# Power.net
KiCad netlist of a schematic drawn in Altium Designer
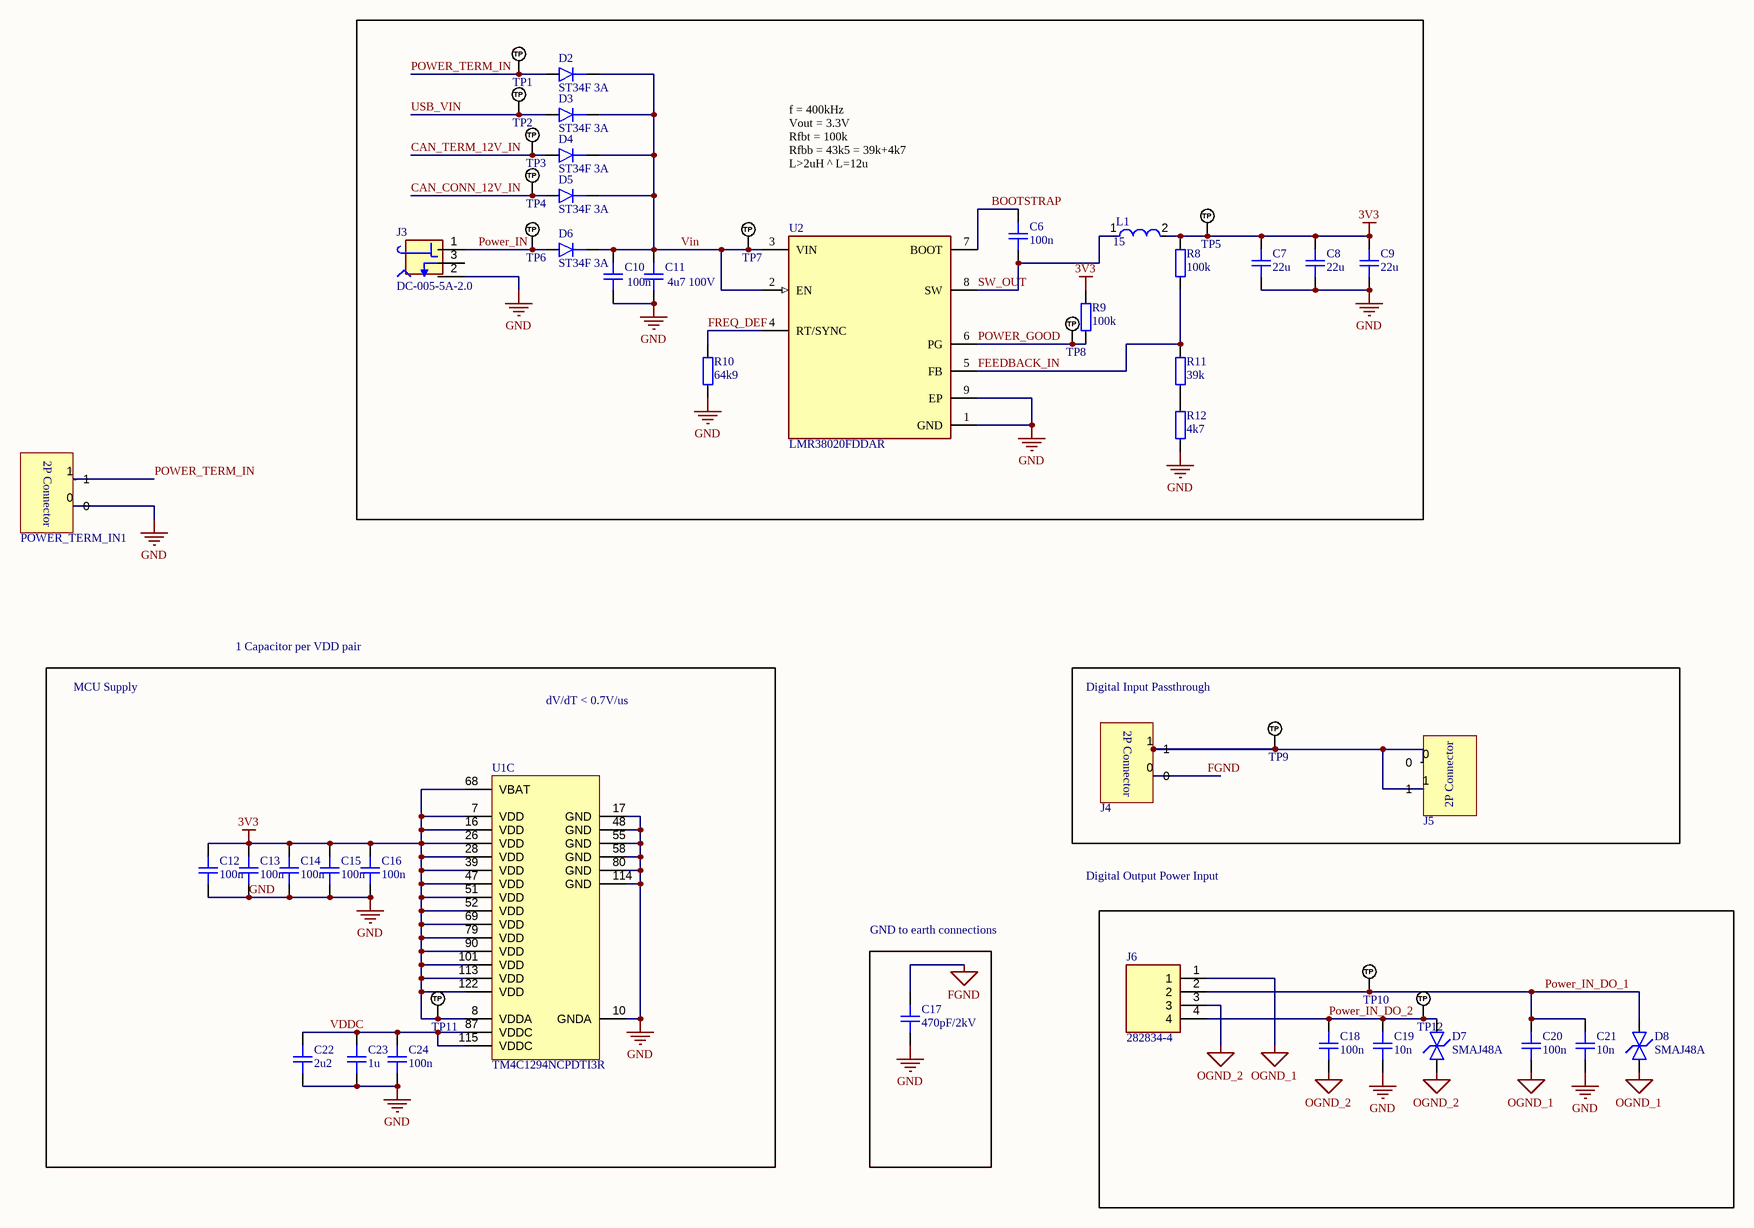
[diagram p0: Power.SchDoc]

(export (version "E")
  (design (tool "Eeschema 10.0.6"))
  (components
    (comp (ref "C6")
      (value "100n")
      (footprint "CAP_0402")
      (description "Capacitor SMD 0402")
      (libsource (lib "Schematic-Lib-PhilsLab") (part "CAP_0402"))
    )
    (comp (ref "C7")
      (value "22u")
      (footprint "CAP_1206")
      (description "Capacitor SMD 1206")
      (libsource (lib "Schematic-Lib-PhilsLab") (part "CAP_1206"))
    )
    (comp (ref "C8")
      (value "22u")
      (footprint "CAP_1206")
      (description "Capacitor SMD 1206")
      (libsource (lib "Schematic-Lib-PhilsLab") (part "CAP_1206"))
    )
    (comp (ref "C9")
      (value "22u")
      (footprint "CAP_1206")
      (description "Capacitor SMD 1206")
      (libsource (lib "Schematic-Lib-PhilsLab") (part "CAP_1206"))
    )
    (comp (ref "C10")
      (value "100n")
      (footprint "CAP_1206")
      (description "Capacitor SMD 1206")
      (libsource (lib "Schematic-Lib-PhilsLab") (part "CAP_1206"))
    )
    (comp (ref "C11")
      (value "4u7 100V")
      (footprint "CAP_1206")
      (description "Capacitor SMD 1206")
      (libsource (lib "Schematic-Lib-PhilsLab") (part "CAP_1206"))
    )
    (comp (ref "C12")
      (value "100n")
      (footprint "CAP_0402")
      (description "Capacitor SMD 0402")
      (libsource (lib "Schematic-Lib-PhilsLab") (part "CAP_0402"))
    )
    (comp (ref "C13")
      (value "100n")
      (footprint "CAP_0402")
      (description "Capacitor SMD 0402")
      (libsource (lib "Schematic-Lib-PhilsLab") (part "CAP_0402"))
    )
    (comp (ref "C14")
      (value "100n")
      (footprint "CAP_0402")
      (description "Capacitor SMD 0402")
      (libsource (lib "Schematic-Lib-PhilsLab") (part "CAP_0402"))
    )
    (comp (ref "C15")
      (value "100n")
      (footprint "CAP_0402")
      (description "Capacitor SMD 0402")
      (libsource (lib "Schematic-Lib-PhilsLab") (part "CAP_0402"))
    )
    (comp (ref "C16")
      (value "100n")
      (footprint "CAP_0402")
      (description "Capacitor SMD 0402")
      (libsource (lib "Schematic-Lib-PhilsLab") (part "CAP_0402"))
    )
    (comp (ref "C17")
      (value "470pF/2kV")
      (footprint "CAP_1206")
      (description "Capacitor SMD 1206")
      (libsource (lib "Schematic-Lib-PhilsLab") (part "CAP_1206"))
    )
    (comp (ref "C18")
      (value "100n")
      (footprint "CAP_0603")
      (description "Capacitor SMD 0603")
      (libsource (lib "Schematic-Lib-PhilsLab") (part "CAP_0603"))
    )
    (comp (ref "C19")
      (value "10n")
      (footprint "CAP_0603")
      (description "Capacitor SMD 0603")
      (libsource (lib "Schematic-Lib-PhilsLab") (part "CAP_0603"))
    )
    (comp (ref "C20")
      (value "100n")
      (footprint "CAP_0603")
      (description "Capacitor SMD 0603")
      (libsource (lib "Schematic-Lib-PhilsLab") (part "CAP_0603"))
    )
    (comp (ref "C21")
      (value "10n")
      (footprint "CAP_0603")
      (description "Capacitor SMD 0603")
      (libsource (lib "Schematic-Lib-PhilsLab") (part "CAP_0603"))
    )
    (comp (ref "C22")
      (value "2u2")
      (footprint "CAP_0402")
      (description "Capacitor SMD 0402")
      (libsource (lib "Schematic-Lib-PhilsLab") (part "CAP_0402"))
    )
    (comp (ref "C23")
      (value "1u")
      (footprint "CAP_0402")
      (description "Capacitor SMD 0402")
      (libsource (lib "Schematic-Lib-PhilsLab") (part "CAP_0402"))
    )
    (comp (ref "C24")
      (value "100n")
      (footprint "CAP_0402")
      (description "Capacitor SMD 0402")
      (libsource (lib "Schematic-Lib-PhilsLab") (part "CAP_0402"))
    )
    (comp (ref "D2")
      (value "ST34F 3A")
      (footprint "DO-214AC-2 (SMA)")
      (description "Diode SMD SMA (DO-214AA)")
      (libsource (lib "Schematic-Lib-PhilsLab") (part "D_SMA"))
    )
    (comp (ref "D3")
      (value "ST34F 3A")
      (footprint "DO-214AC-2 (SMA)")
      (description "Diode SMD SMA (DO-214AA)")
      (libsource (lib "Schematic-Lib-PhilsLab") (part "D_SMA"))
    )
    (comp (ref "D4")
      (value "ST34F 3A")
      (footprint "DO-214AC-2 (SMA)")
      (description "Diode SMD SMA (DO-214AA)")
      (libsource (lib "Schematic-Lib-PhilsLab") (part "D_SMA"))
    )
    (comp (ref "D5")
      (value "ST34F 3A")
      (footprint "DO-214AC-2 (SMA)")
      (description "Diode SMD SMA (DO-214AA)")
      (libsource (lib "Schematic-Lib-PhilsLab") (part "D_SMA"))
    )
    (comp (ref "D6")
      (value "ST34F 3A")
      (footprint "DO-214AC-2 (SMA)")
      (description "Diode SMD SMA (DO-214AA)")
      (libsource (lib "Schematic-Lib-PhilsLab") (part "D_SMA"))
    )
    (comp (ref "D7")
      (value "SMAJ48A")
      (footprint "DO-214AC-2 (SMA)")
      (description "Diode TVS / ESD Bidirectional SMC (DO-214AB)")
      (libsource (lib "Schematic-Lib-PhilsLab") (part "D_TVS_BI_SMC"))
    )
    (comp (ref "D8")
      (value "SMAJ48A")
      (footprint "DO-214AC-2 (SMA)")
      (description "Diode TVS / ESD Bidirectional SMC (DO-214AB)")
      (libsource (lib "Schematic-Lib-PhilsLab") (part "D_TVS_BI_SMC"))
    )
    (comp (ref "J3")
      (value "DC-005-5A-2.0")
      (footprint "XKB_DC-005-5A-2.0")
      (description "DC Power Receptacle Jack, Through Holeï¼ŒRight Angle")
      (fields (field (name "MF") "XKB Industrial Precision"))
      (libsource (lib "DIGI2") (part "DC-005-5A-2.0"))
    )
    (comp (ref "J4")
      (value "DG308-2.54-02P-12-00AH")
      (footprint "DG308-2.54-02P-12-00AH-Footprint-1")
      (description "1x2P -40℃~+105℃ 8A 130V Green 18~26 Straight 2.54mm 0.5~1 1 2 Plugin,P=2.54mm Screw terminal ROHS")
      (libsource (lib "DIGI2") (part "DG308-2.54-02P-12-00AH"))
    )
    (comp (ref "J5")
      (value "DG308-2.54-02P-12-00AH")
      (footprint "DG308-2.54-02P-12-00AH-Footprint-1")
      (description "1x2P -40℃~+105℃ 8A 130V Green 18~26 Straight 2.54mm 0.5~1 1 2 Plugin,P=2.54mm Screw terminal ROHS")
      (libsource (lib "") (part "DG308-2.54-02P-12-00AH_1"))
    )
    (comp (ref "J6")
      (value "282834-4")
      (footprint "TE_282834-4")
      (description "4 Position Wire to Board Terminal Block Horizontal with Board 0.100 (2.54mm) Through Hole")
      (fields (field (name "MF") "TE Connectivity"))
      (libsource (lib "282834-4") (part "282834-4"))
    )
    (comp (ref "L1")
      (value "15")
      (footprint "FP-SPM10040-MFG")
      (description "FIXED IND 2.2UH 16.7A 7.46MOHM")
      (fields (field (name "MANUFACTURER") "TDK") (field (name "TOLERANCE") "20%"))
      (libsource (lib "Altium Content Vault") (part "725321dda6339637d4d059423bc1c3c"))
    )
    (comp (ref "POWER_TERM_IN1")
      (value "DG308-2.54-02P-12-00AH")
      (footprint "DG308-2.54-02P-12-00AH-Footprint-1")
      (description "1x2P -40℃~+105℃ 8A 130V Green 18~26 Straight 2.54mm 0.5~1 1 2 Plugin,P=2.54mm Screw terminal ROHS")
      (libsource (lib "DIGI2") (part "DG308-2.54-02P-12-00AH"))
    )
    (comp (ref "R8")
      (value "100k")
      (footprint "RES_0402")
      (description "Resistor SMD 0402")
      (libsource (lib "Schematic-Lib-PhilsLab") (part "RES_0402"))
    )
    (comp (ref "R9")
      (value "100k")
      (footprint "RES_0402")
      (description "Resistor SMD 0402")
      (libsource (lib "Schematic-Lib-PhilsLab") (part "RES_0402"))
    )
    (comp (ref "R10")
      (value "64k9")
      (footprint "RES_0402")
      (description "Resistor SMD 0402")
      (libsource (lib "Schematic-Lib-PhilsLab") (part "RES_0402"))
    )
    (comp (ref "R11")
      (value "39k")
      (footprint "RES_0402")
      (description "Resistor SMD 0402")
      (libsource (lib "Schematic-Lib-PhilsLab") (part "RES_0402"))
    )
    (comp (ref "R12")
      (value "4k7")
      (footprint "RES_0402")
      (description "Resistor SMD 0402")
      (libsource (lib "Schematic-Lib-PhilsLab") (part "RES_0402"))
    )
    (comp (ref "TP1")
      (value "TP_NOBOM")
      (footprint "PAD_RND_1MM")
      (description "Test Point Round 1mm (NO BOM)")
      (libsource (lib "Schematic-Lib-PhilsLab") (part "TEST_POINT_RND_1MM"))
    )
    (comp (ref "TP2")
      (value "TP_NOBOM")
      (footprint "PAD_RND_1MM")
      (description "Test Point Round 1mm (NO BOM)")
      (libsource (lib "Schematic-Lib-PhilsLab") (part "TEST_POINT_RND_1MM"))
    )
    (comp (ref "TP3")
      (value "TP_NOBOM")
      (footprint "PAD_RND_1MM")
      (description "Test Point Round 1mm (NO BOM)")
      (libsource (lib "Schematic-Lib-PhilsLab") (part "TEST_POINT_RND_1MM"))
    )
    (comp (ref "TP4")
      (value "TP_NOBOM")
      (footprint "PAD_RND_1MM")
      (description "Test Point Round 1mm (NO BOM)")
      (libsource (lib "Schematic-Lib-PhilsLab") (part "TEST_POINT_RND_1MM"))
    )
    (comp (ref "TP5")
      (value "TP_NOBOM")
      (footprint "PAD_RND_1MM")
      (description "Test Point Round 1mm (NO BOM)")
      (libsource (lib "Schematic-Lib-PhilsLab") (part "TEST_POINT_RND_1MM"))
    )
    (comp (ref "TP6")
      (value "TP_NOBOM")
      (footprint "PAD_RND_1MM")
      (description "Test Point Round 1mm (NO BOM)")
      (libsource (lib "Schematic-Lib-PhilsLab") (part "TEST_POINT_RND_1MM"))
    )
    (comp (ref "TP7")
      (value "TP_NOBOM")
      (footprint "PAD_RND_1MM")
      (description "Test Point Round 1mm (NO BOM)")
      (libsource (lib "Schematic-Lib-PhilsLab") (part "TEST_POINT_RND_1MM"))
    )
    (comp (ref "TP8")
      (value "TP_NOBOM")
      (footprint "PAD_RND_1MM")
      (description "Test Point Round 1mm (NO BOM)")
      (libsource (lib "Schematic-Lib-PhilsLab") (part "TEST_POINT_RND_1MM"))
    )
    (comp (ref "TP9")
      (value "TP_NOBOM")
      (footprint "PAD_RND_1MM")
      (description "Test Point Round 1mm (NO BOM)")
      (libsource (lib "Schematic-Lib-PhilsLab") (part "TEST_POINT_RND_1MM"))
    )
    (comp (ref "TP10")
      (value "TP_NOBOM")
      (footprint "PAD_RND_1MM")
      (description "Test Point Round 1mm (NO BOM)")
      (libsource (lib "Schematic-Lib-PhilsLab") (part "TEST_POINT_RND_1MM"))
    )
    (comp (ref "TP11")
      (value "TP_NOBOM")
      (footprint "PAD_RND_1MM")
      (description "Test Point Round 1mm (NO BOM)")
      (libsource (lib "Schematic-Lib-PhilsLab") (part "TEST_POINT_RND_1MM"))
    )
    (comp (ref "TP12")
      (value "TP_NOBOM")
      (footprint "PAD_RND_1MM")
      (description "Test Point Round 1mm (NO BOM)")
      (libsource (lib "Schematic-Lib-PhilsLab") (part "TEST_POINT_RND_1MM"))
    )
    (comp (ref "U1")
      (value "TM4C1294NCPDTI3R")
      (footprint "PDT0128A_M")
      (fields (field (name "MANUFACTURER") "Texas Instruments"))
      (libsource (lib "Altium Content Vault") (part "TI-TM4C1294NCPDT-128"))
    )
    (comp (ref "U2")
      (value "LMR38020FDDAR")
      (footprint "FP-DDA0008E-IPC_C")
      (description "4.2-V to 80-V, 2-A Synchronous Buck Converter with 40-µA IQ")
      (libsource (lib "Altium Content Vault") (part "1aefaab7de6e8c55c0c37b595fa5634"))
    )
  )
  (nets
    (net (code "1") (name "/BOOTSTRAP") (class "Default")
      (node (ref "C6") (pin "2") (pinfunction "2_2") (pintype "passive"))
      (node (ref "U2") (pin "7") (pinfunction "BOOT_7") (pintype "passive"))
    )
    (net (code "2") (name "/CAN_CONN_12V_IN") (class "Default")
      (node (ref "D5") (pin "A") (pinfunction "A_A") (pintype "passive"))
      (node (ref "TP4") (pin "1") (pinfunction "TP_1") (pintype "passive"))
    )
    (net (code "3") (name "/CAN_TERM_12V_IN") (class "Default")
      (node (ref "D4") (pin "A") (pinfunction "A_A") (pintype "passive"))
      (node (ref "TP3") (pin "1") (pinfunction "TP_1") (pintype "passive"))
    )
    (net (code "4") (name "/FEEDBACK_IN") (class "Default")
      (node (ref "R11") (pin "2") (pinfunction "2_2") (pintype "passive"))
      (node (ref "R8") (pin "1") (pinfunction "1_1") (pintype "passive"))
      (node (ref "U2") (pin "5") (pinfunction "FB_5") (pintype "passive"))
    )
    (net (code "5") (name "/FREQ_DEF") (class "Default")
      (node (ref "R10") (pin "2") (pinfunction "2_2") (pintype "passive"))
      (node (ref "U2") (pin "4") (pinfunction "RT/SYNC_4") (pintype "passive"))
    )
    (net (code "6") (name "/POWER_GOOD") (class "Default")
      (node (ref "R9") (pin "1") (pinfunction "1_1") (pintype "passive"))
      (node (ref "TP8") (pin "1") (pinfunction "TP_1") (pintype "passive"))
      (node (ref "U2") (pin "6") (pinfunction "PG_6") (pintype "open_collector"))
    )
    (net (code "7") (name "/POWER_TERM_IN") (class "Default")
      (node (ref "D2") (pin "A") (pinfunction "A_A") (pintype "passive"))
      (node (ref "POWER_TERM_IN1") (pin "1") (pinfunction "1_1") (pintype "passive"))
      (node (ref "TP1") (pin "1") (pinfunction "TP_1") (pintype "passive"))
    )
    (net (code "8") (name "/Power_IN") (class "Default")
      (node (ref "D6") (pin "A") (pinfunction "A_A") (pintype "passive"))
      (node (ref "J3") (pin "1") (pinfunction "1_1") (pintype "passive"))
      (node (ref "TP6") (pin "1") (pinfunction "TP_1") (pintype "passive"))
    )
    (net (code "9") (name "/Power_IN_DO_1") (class "Default")
      (node (ref "C20") (pin "2") (pinfunction "2_2") (pintype "passive"))
      (node (ref "C21") (pin "2") (pinfunction "2_2") (pintype "passive"))
      (node (ref "D8") (pin "K") (pinfunction "K_K") (pintype "passive"))
      (node (ref "J6") (pin "2") (pinfunction "2_2") (pintype "passive"))
      (node (ref "TP10") (pin "1") (pinfunction "TP_1") (pintype "passive"))
    )
    (net (code "10") (name "/Power_IN_DO_2") (class "Default")
      (node (ref "C18") (pin "2") (pinfunction "2_2") (pintype "passive"))
      (node (ref "C19") (pin "2") (pinfunction "2_2") (pintype "passive"))
      (node (ref "D7") (pin "K") (pinfunction "K_K") (pintype "passive"))
      (node (ref "J6") (pin "4") (pinfunction "4_4") (pintype "passive"))
      (node (ref "TP12") (pin "1") (pinfunction "TP_1") (pintype "passive"))
    )
    (net (code "11") (name "/SW_OUT") (class "Default")
      (node (ref "C6") (pin "1") (pinfunction "1_1") (pintype "passive"))
      (node (ref "L1") (pin "1") (pinfunction "1_1") (pintype "passive"))
      (node (ref "U2") (pin "8") (pinfunction "SW_8") (pintype "passive"))
    )
    (net (code "12") (name "/USB_VIN") (class "Default")
      (node (ref "D3") (pin "A") (pinfunction "A_A") (pintype "passive"))
      (node (ref "TP2") (pin "1") (pinfunction "TP_1") (pintype "passive"))
    )
    (net (code "13") (name "/VDDC") (class "Default")
      (node (ref "C22") (pin "2") (pinfunction "2_2") (pintype "passive"))
      (node (ref "C23") (pin "2") (pinfunction "2_2") (pintype "passive"))
      (node (ref "C24") (pin "2") (pinfunction "2_2") (pintype "passive"))
      (node (ref "U1") (pin "115") (pinfunction "VDDC_115") (pintype "power_in"))
      (node (ref "U1") (pin "87") (pinfunction "VDDC_87") (pintype "power_in"))
    )
    (net (code "14") (name "/Vin") (class "Default")
      (node (ref "C10") (pin "2") (pinfunction "2_2") (pintype "passive"))
      (node (ref "C11") (pin "2") (pinfunction "2_2") (pintype "passive"))
      (node (ref "D2") (pin "K") (pinfunction "K_K") (pintype "passive"))
      (node (ref "D3") (pin "K") (pinfunction "K_K") (pintype "passive"))
      (node (ref "D4") (pin "K") (pinfunction "K_K") (pintype "passive"))
      (node (ref "D5") (pin "K") (pinfunction "K_K") (pintype "passive"))
      (node (ref "D6") (pin "K") (pinfunction "K_K") (pintype "passive"))
      (node (ref "TP7") (pin "1") (pinfunction "TP_1") (pintype "passive"))
      (node (ref "U2") (pin "2") (pinfunction "EN_2") (pintype "input"))
      (node (ref "U2") (pin "3") (pinfunction "VIN_3") (pintype "power_in"))
    )
    (net (code "15") (name "3V3") (class "Default")
      (node (ref "C12") (pin "2") (pinfunction "2_2") (pintype "passive"))
      (node (ref "C13") (pin "2") (pinfunction "2_2") (pintype "passive"))
      (node (ref "C14") (pin "2") (pinfunction "2_2") (pintype "passive"))
      (node (ref "C15") (pin "2") (pinfunction "2_2") (pintype "passive"))
      (node (ref "C16") (pin "2") (pinfunction "2_2") (pintype "passive"))
      (node (ref "C7") (pin "2") (pinfunction "2_2") (pintype "passive"))
      (node (ref "C8") (pin "2") (pinfunction "2_2") (pintype "passive"))
      (node (ref "C9") (pin "2") (pinfunction "2_2") (pintype "passive"))
      (node (ref "L1") (pin "2") (pinfunction "2_2") (pintype "passive"))
      (node (ref "R8") (pin "2") (pinfunction "2_2") (pintype "passive"))
      (node (ref "R9") (pin "2") (pinfunction "2_2") (pintype "passive"))
      (node (ref "TP11") (pin "1") (pinfunction "TP_1") (pintype "passive"))
      (node (ref "TP5") (pin "1") (pinfunction "TP_1") (pintype "passive"))
      (node (ref "U1") (pin "101") (pinfunction "VDD_101") (pintype "power_in"))
      (node (ref "U1") (pin "113") (pinfunction "VDD_113") (pintype "power_in"))
      (node (ref "U1") (pin "122") (pinfunction "VDD_122") (pintype "power_in"))
      (node (ref "U1") (pin "16") (pinfunction "VDD_16") (pintype "power_in"))
      (node (ref "U1") (pin "26") (pinfunction "VDD_26") (pintype "power_in"))
      (node (ref "U1") (pin "28") (pinfunction "VDD_28") (pintype "power_in"))
      (node (ref "U1") (pin "39") (pinfunction "VDD_39") (pintype "power_in"))
      (node (ref "U1") (pin "47") (pinfunction "VDD_47") (pintype "power_in"))
      (node (ref "U1") (pin "51") (pinfunction "VDD_51") (pintype "power_in"))
      (node (ref "U1") (pin "52") (pinfunction "VDD_52") (pintype "power_in"))
      (node (ref "U1") (pin "68") (pinfunction "VBAT_68") (pintype "power_in"))
      (node (ref "U1") (pin "69") (pinfunction "VDD_69") (pintype "power_in"))
      (node (ref "U1") (pin "7") (pinfunction "VDD_7") (pintype "power_in"))
      (node (ref "U1") (pin "79") (pinfunction "VDD_79") (pintype "power_in"))
      (node (ref "U1") (pin "8") (pinfunction "VDDA_8") (pintype "power_in"))
      (node (ref "U1") (pin "90") (pinfunction "VDD_90") (pintype "power_in"))
    )
    (net (code "16") (name "FGND") (class "Default")
      (node (ref "C17") (pin "2") (pinfunction "2_2") (pintype "passive"))
      (node (ref "J4") (pin "0") (pinfunction "0_0") (pintype "passive"))
    )
    (net (code "17") (name "GND") (class "Default")
      (node (ref "C10") (pin "1") (pinfunction "1_1") (pintype "passive"))
      (node (ref "C11") (pin "1") (pinfunction "1_1") (pintype "passive"))
      (node (ref "C12") (pin "1") (pinfunction "1_1") (pintype "passive"))
      (node (ref "C13") (pin "1") (pinfunction "1_1") (pintype "passive"))
      (node (ref "C14") (pin "1") (pinfunction "1_1") (pintype "passive"))
      (node (ref "C15") (pin "1") (pinfunction "1_1") (pintype "passive"))
      (node (ref "C16") (pin "1") (pinfunction "1_1") (pintype "passive"))
      (node (ref "C17") (pin "1") (pinfunction "1_1") (pintype "passive"))
      (node (ref "C19") (pin "1") (pinfunction "1_1") (pintype "passive"))
      (node (ref "C21") (pin "1") (pinfunction "1_1") (pintype "passive"))
      (node (ref "C22") (pin "1") (pinfunction "1_1") (pintype "passive"))
      (node (ref "C23") (pin "1") (pinfunction "1_1") (pintype "passive"))
      (node (ref "C24") (pin "1") (pinfunction "1_1") (pintype "passive"))
      (node (ref "C7") (pin "1") (pinfunction "1_1") (pintype "passive"))
      (node (ref "C8") (pin "1") (pinfunction "1_1") (pintype "passive"))
      (node (ref "C9") (pin "1") (pinfunction "1_1") (pintype "passive"))
      (node (ref "J3") (pin "2") (pinfunction "2_2") (pintype "passive"))
      (node (ref "POWER_TERM_IN1") (pin "0") (pinfunction "0_0") (pintype "passive"))
      (node (ref "R10") (pin "1") (pinfunction "1_1") (pintype "passive"))
      (node (ref "R12") (pin "1") (pinfunction "1_1") (pintype "passive"))
      (node (ref "U1") (pin "10") (pinfunction "GNDA_10") (pintype "power_in"))
      (node (ref "U1") (pin "114") (pinfunction "GND_114") (pintype "power_in"))
      (node (ref "U1") (pin "17") (pinfunction "GND_17") (pintype "power_in"))
      (node (ref "U1") (pin "48") (pinfunction "GND_48") (pintype "power_in"))
      (node (ref "U1") (pin "55") (pinfunction "GND_55") (pintype "power_in"))
      (node (ref "U1") (pin "58") (pinfunction "GND_58") (pintype "power_in"))
      (node (ref "U1") (pin "80") (pinfunction "GND_80") (pintype "power_in"))
      (node (ref "U2") (pin "1") (pinfunction "GND_1") (pintype "power_in"))
      (node (ref "U2") (pin "9") (pinfunction "EP_9") (pintype "passive"))
    )
    (net (code "18") (name "Net-(R11-Pad1)") (class "Default")
      (node (ref "R11") (pin "1") (pinfunction "1_1") (pintype "passive"))
      (node (ref "R12") (pin "2") (pinfunction "2_2") (pintype "passive"))
    )
    (net (code "19") (name "Net-(TP9-TP)") (class "Default")
      (node (ref "J4") (pin "1") (pinfunction "1_1") (pintype "passive"))
      (node (ref "J5") (pin "0") (pinfunction "0_0") (pintype "passive"))
      (node (ref "J5") (pin "1") (pinfunction "1_1") (pintype "passive"))
      (node (ref "TP9") (pin "1") (pinfunction "TP_1") (pintype "passive"))
    )
    (net (code "20") (name "OGND_1") (class "Default")
      (node (ref "C20") (pin "1") (pinfunction "1_1") (pintype "passive"))
      (node (ref "D8") (pin "A") (pinfunction "A_A") (pintype "passive"))
      (node (ref "J6") (pin "1") (pinfunction "1_1") (pintype "passive"))
    )
    (net (code "21") (name "OGND_2") (class "Default")
      (node (ref "C18") (pin "1") (pinfunction "1_1") (pintype "passive"))
      (node (ref "D7") (pin "A") (pinfunction "A_A") (pintype "passive"))
      (node (ref "J6") (pin "3") (pinfunction "3_3") (pintype "passive"))
    )
    (net (code "22") (name "unconnected-(J3-Pad3)") (class "Default")
      (node (ref "J3") (pin "3") (pinfunction "3_3") (pintype "passive"))
    )
  )
)
